# SCH_cube_2025-02-01.net
KiCad netlist of a schematic drawn in EasyEDA
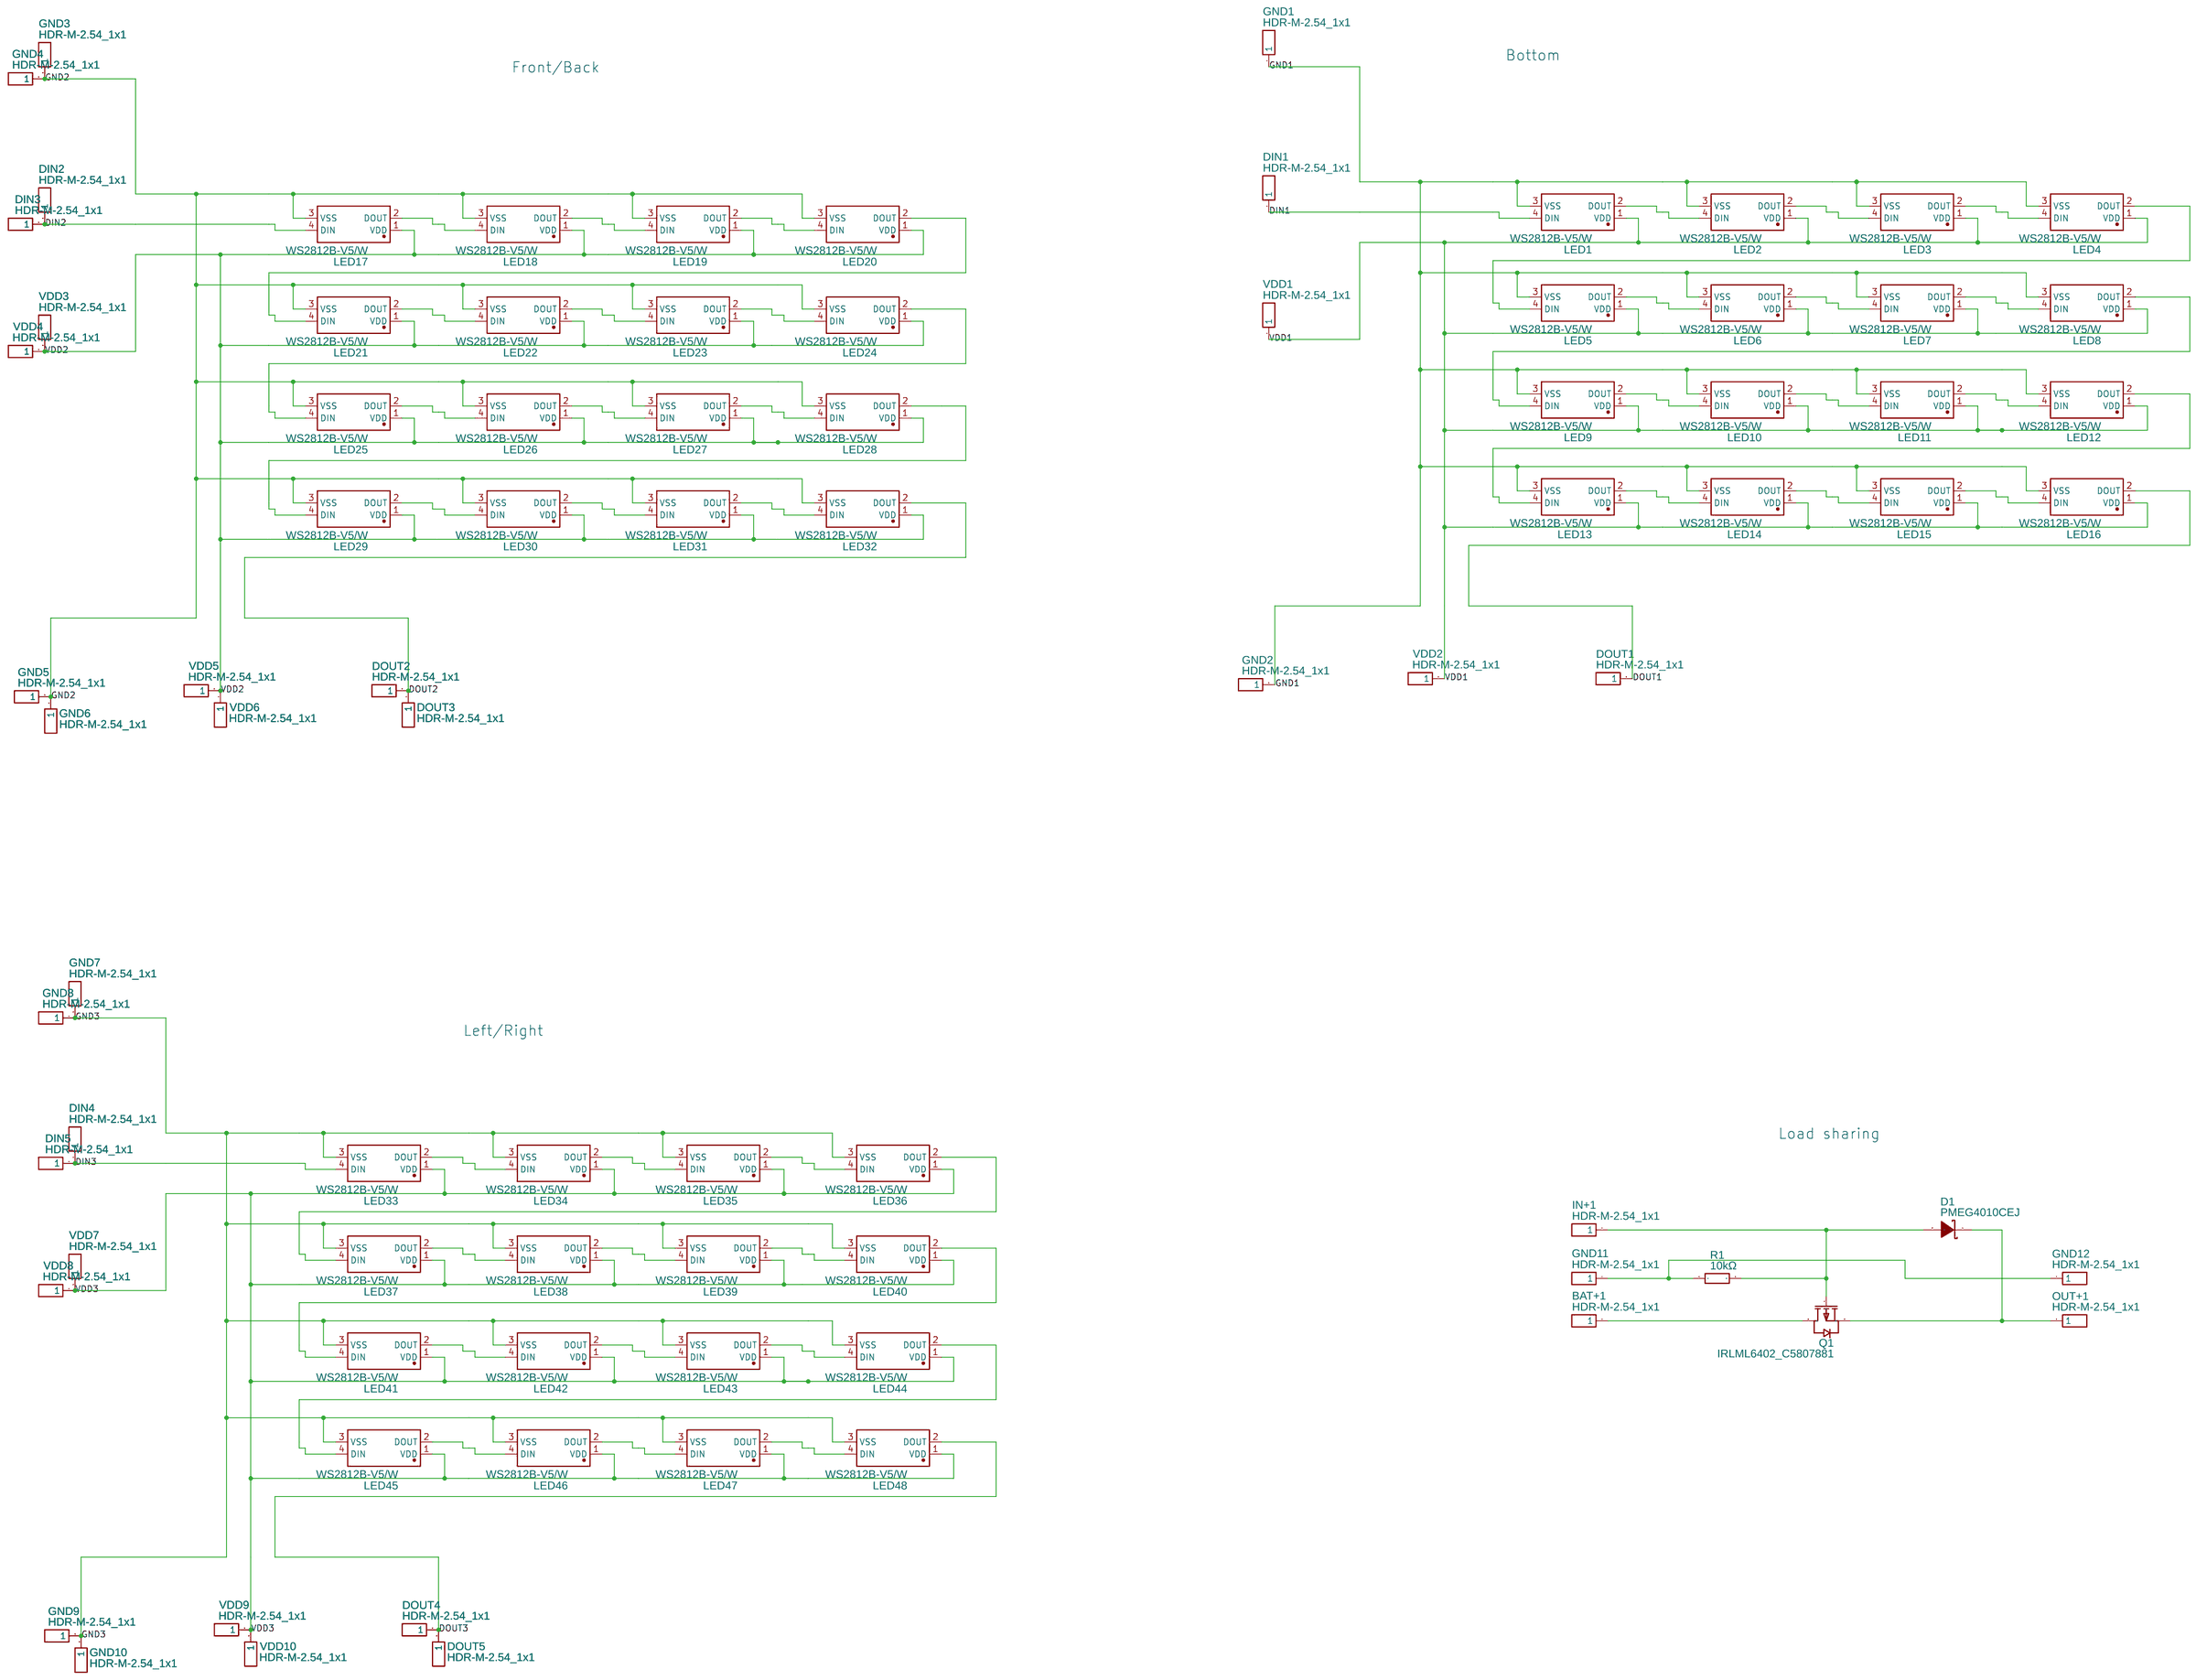
[diagram p0: schematic sheet]

(export (version "E")
  (design (tool "Eeschema 10.0.6"))
  (components
    (comp (ref "BAT+1") (value "HDR-M-2.54_1x1") (libsource (lib "") (part "HDR-M-2.54_1x1_12")))
    (comp (ref "D1")
      (value "PMEG4010CEJ")
      (fields
        (field (name "Manufacturer Part") "PMEG4010CEJ,115")
        (field (name "Manufacturer") "Nexperia(安世)")
      )
      (libsource (lib "") (part "PMEG4010CEJ"))
    )
    (comp (ref "DIN1") (value "HDR-M-2.54_1x1") (libsource (lib "") (part "HDR-M-2.54_1x1_4")))
    (comp (ref "DIN2") (value "HDR-M-2.54_1x1") (libsource (lib "") (part "HDR-M-2.54_1x1_4")))
    (comp (ref "DIN3") (value "HDR-M-2.54_1x1") (libsource (lib "") (part "HDR-M-2.54_1x1_3")))
    (comp (ref "DIN4") (value "HDR-M-2.54_1x1") (libsource (lib "") (part "HDR-M-2.54_1x1_4")))
    (comp (ref "DIN5") (value "HDR-M-2.54_1x1") (libsource (lib "") (part "HDR-M-2.54_1x1_3")))
    (comp (ref "DOUT1") (value "HDR-M-2.54_1x1") (libsource (lib "") (part "HDR-M-2.54_1x1_2")))
    (comp (ref "DOUT2") (value "HDR-M-2.54_1x1") (libsource (lib "") (part "HDR-M-2.54_1x1_2")))
    (comp (ref "DOUT3") (value "HDR-M-2.54_1x1") (libsource (lib "") (part "HDR-M-2.54_1x1_1")))
    (comp (ref "DOUT4") (value "HDR-M-2.54_1x1") (libsource (lib "") (part "HDR-M-2.54_1x1_2")))
    (comp (ref "DOUT5") (value "HDR-M-2.54_1x1") (libsource (lib "") (part "HDR-M-2.54_1x1_1")))
    (comp (ref "GND1") (value "HDR-M-2.54_1x1") (libsource (lib "") (part "HDR-M-2.54_1x1_6")))
    (comp (ref "GND2") (value "HDR-M-2.54_1x1") (libsource (lib "") (part "HDR-M-2.54_1x1_5")))
    (comp (ref "GND3") (value "HDR-M-2.54_1x1") (libsource (lib "") (part "HDR-M-2.54_1x1_6")))
    (comp (ref "GND4") (value "HDR-M-2.54_1x1") (libsource (lib "") (part "HDR-M-2.54_1x1_5")))
    (comp (ref "GND5") (value "HDR-M-2.54_1x1") (libsource (lib "") (part "HDR-M-2.54_1x1_5")))
    (comp (ref "GND6") (value "HDR-M-2.54_1x1") (libsource (lib "") (part "HDR-M-2.54_1x1_10")))
    (comp (ref "GND7") (value "HDR-M-2.54_1x1") (libsource (lib "") (part "HDR-M-2.54_1x1_6")))
    (comp (ref "GND8") (value "HDR-M-2.54_1x1") (libsource (lib "") (part "HDR-M-2.54_1x1_5")))
    (comp (ref "GND9") (value "HDR-M-2.54_1x1") (libsource (lib "") (part "HDR-M-2.54_1x1_5")))
    (comp (ref "GND10") (value "HDR-M-2.54_1x1") (libsource (lib "") (part "HDR-M-2.54_1x1_10")))
    (comp (ref "GND11") (value "HDR-M-2.54_1x1") (libsource (lib "") (part "HDR-M-2.54_1x1_5")))
    (comp (ref "GND12") (value "HDR-M-2.54_1x1") (libsource (lib "") (part "HDR-M-2.54_1x1_8")))
    (comp (ref "IN+1") (value "HDR-M-2.54_1x1") (libsource (lib "") (part "HDR-M-2.54_1x1_9")))
    (comp (ref "LED1")
      (value "WS2812B-V5/W")
      (fields (field (name "Manufacturer") "worldsemi"))
      (libsource (lib "") (part "WS2812B-V5/W"))
    )
    (comp (ref "LED2")
      (value "WS2812B-V5/W")
      (fields (field (name "Manufacturer") "worldsemi"))
      (libsource (lib "") (part "WS2812B-V5/W"))
    )
    (comp (ref "LED3")
      (value "WS2812B-V5/W")
      (fields (field (name "Manufacturer") "worldsemi"))
      (libsource (lib "") (part "WS2812B-V5/W"))
    )
    (comp (ref "LED4")
      (value "WS2812B-V5/W")
      (fields (field (name "Manufacturer") "worldsemi"))
      (libsource (lib "") (part "WS2812B-V5/W"))
    )
    (comp (ref "LED5")
      (value "WS2812B-V5/W")
      (fields (field (name "Manufacturer") "worldsemi"))
      (libsource (lib "") (part "WS2812B-V5/W"))
    )
    (comp (ref "LED6")
      (value "WS2812B-V5/W")
      (fields (field (name "Manufacturer") "worldsemi"))
      (libsource (lib "") (part "WS2812B-V5/W"))
    )
    (comp (ref "LED7")
      (value "WS2812B-V5/W")
      (fields (field (name "Manufacturer") "worldsemi"))
      (libsource (lib "") (part "WS2812B-V5/W"))
    )
    (comp (ref "LED8")
      (value "WS2812B-V5/W")
      (fields (field (name "Manufacturer") "worldsemi"))
      (libsource (lib "") (part "WS2812B-V5/W"))
    )
    (comp (ref "LED9")
      (value "WS2812B-V5/W")
      (fields (field (name "Manufacturer") "worldsemi"))
      (libsource (lib "") (part "WS2812B-V5/W"))
    )
    (comp (ref "LED10")
      (value "WS2812B-V5/W")
      (fields (field (name "Manufacturer") "worldsemi"))
      (libsource (lib "") (part "WS2812B-V5/W"))
    )
    (comp (ref "LED11")
      (value "WS2812B-V5/W")
      (fields (field (name "Manufacturer") "worldsemi"))
      (libsource (lib "") (part "WS2812B-V5/W"))
    )
    (comp (ref "LED12")
      (value "WS2812B-V5/W")
      (fields (field (name "Manufacturer") "worldsemi"))
      (libsource (lib "") (part "WS2812B-V5/W"))
    )
    (comp (ref "LED13")
      (value "WS2812B-V5/W")
      (fields (field (name "Manufacturer") "worldsemi"))
      (libsource (lib "") (part "WS2812B-V5/W"))
    )
    (comp (ref "LED14")
      (value "WS2812B-V5/W")
      (fields (field (name "Manufacturer") "worldsemi"))
      (libsource (lib "") (part "WS2812B-V5/W"))
    )
    (comp (ref "LED15")
      (value "WS2812B-V5/W")
      (fields (field (name "Manufacturer") "worldsemi"))
      (libsource (lib "") (part "WS2812B-V5/W"))
    )
    (comp (ref "LED16")
      (value "WS2812B-V5/W")
      (fields (field (name "Manufacturer") "worldsemi"))
      (libsource (lib "") (part "WS2812B-V5/W"))
    )
    (comp (ref "LED17")
      (value "WS2812B-V5/W")
      (fields (field (name "Manufacturer") "worldsemi"))
      (libsource (lib "") (part "WS2812B-V5/W"))
    )
    (comp (ref "LED18")
      (value "WS2812B-V5/W")
      (fields (field (name "Manufacturer") "worldsemi"))
      (libsource (lib "") (part "WS2812B-V5/W"))
    )
    (comp (ref "LED19")
      (value "WS2812B-V5/W")
      (fields (field (name "Manufacturer") "worldsemi"))
      (libsource (lib "") (part "WS2812B-V5/W"))
    )
    (comp (ref "LED20")
      (value "WS2812B-V5/W")
      (fields (field (name "Manufacturer") "worldsemi"))
      (libsource (lib "") (part "WS2812B-V5/W"))
    )
    (comp (ref "LED21")
      (value "WS2812B-V5/W")
      (fields (field (name "Manufacturer") "worldsemi"))
      (libsource (lib "") (part "WS2812B-V5/W"))
    )
    (comp (ref "LED22")
      (value "WS2812B-V5/W")
      (fields (field (name "Manufacturer") "worldsemi"))
      (libsource (lib "") (part "WS2812B-V5/W"))
    )
    (comp (ref "LED23")
      (value "WS2812B-V5/W")
      (fields (field (name "Manufacturer") "worldsemi"))
      (libsource (lib "") (part "WS2812B-V5/W"))
    )
    (comp (ref "LED24")
      (value "WS2812B-V5/W")
      (fields (field (name "Manufacturer") "worldsemi"))
      (libsource (lib "") (part "WS2812B-V5/W"))
    )
    (comp (ref "LED25")
      (value "WS2812B-V5/W")
      (fields (field (name "Manufacturer") "worldsemi"))
      (libsource (lib "") (part "WS2812B-V5/W"))
    )
    (comp (ref "LED26")
      (value "WS2812B-V5/W")
      (fields (field (name "Manufacturer") "worldsemi"))
      (libsource (lib "") (part "WS2812B-V5/W"))
    )
    (comp (ref "LED27")
      (value "WS2812B-V5/W")
      (fields (field (name "Manufacturer") "worldsemi"))
      (libsource (lib "") (part "WS2812B-V5/W"))
    )
    (comp (ref "LED28")
      (value "WS2812B-V5/W")
      (fields (field (name "Manufacturer") "worldsemi"))
      (libsource (lib "") (part "WS2812B-V5/W"))
    )
    (comp (ref "LED29")
      (value "WS2812B-V5/W")
      (fields (field (name "Manufacturer") "worldsemi"))
      (libsource (lib "") (part "WS2812B-V5/W"))
    )
    (comp (ref "LED30")
      (value "WS2812B-V5/W")
      (fields (field (name "Manufacturer") "worldsemi"))
      (libsource (lib "") (part "WS2812B-V5/W"))
    )
    (comp (ref "LED31")
      (value "WS2812B-V5/W")
      (fields (field (name "Manufacturer") "worldsemi"))
      (libsource (lib "") (part "WS2812B-V5/W"))
    )
    (comp (ref "LED32")
      (value "WS2812B-V5/W")
      (fields (field (name "Manufacturer") "worldsemi"))
      (libsource (lib "") (part "WS2812B-V5/W"))
    )
    (comp (ref "LED33")
      (value "WS2812B-V5/W")
      (fields (field (name "Manufacturer") "worldsemi"))
      (libsource (lib "") (part "WS2812B-V5/W"))
    )
    (comp (ref "LED34")
      (value "WS2812B-V5/W")
      (fields (field (name "Manufacturer") "worldsemi"))
      (libsource (lib "") (part "WS2812B-V5/W"))
    )
    (comp (ref "LED35")
      (value "WS2812B-V5/W")
      (fields (field (name "Manufacturer") "worldsemi"))
      (libsource (lib "") (part "WS2812B-V5/W"))
    )
    (comp (ref "LED36")
      (value "WS2812B-V5/W")
      (fields (field (name "Manufacturer") "worldsemi"))
      (libsource (lib "") (part "WS2812B-V5/W"))
    )
    (comp (ref "LED37")
      (value "WS2812B-V5/W")
      (fields (field (name "Manufacturer") "worldsemi"))
      (libsource (lib "") (part "WS2812B-V5/W"))
    )
    (comp (ref "LED38")
      (value "WS2812B-V5/W")
      (fields (field (name "Manufacturer") "worldsemi"))
      (libsource (lib "") (part "WS2812B-V5/W"))
    )
    (comp (ref "LED39")
      (value "WS2812B-V5/W")
      (fields (field (name "Manufacturer") "worldsemi"))
      (libsource (lib "") (part "WS2812B-V5/W"))
    )
    (comp (ref "LED40")
      (value "WS2812B-V5/W")
      (fields (field (name "Manufacturer") "worldsemi"))
      (libsource (lib "") (part "WS2812B-V5/W"))
    )
    (comp (ref "LED41")
      (value "WS2812B-V5/W")
      (fields (field (name "Manufacturer") "worldsemi"))
      (libsource (lib "") (part "WS2812B-V5/W"))
    )
    (comp (ref "LED42")
      (value "WS2812B-V5/W")
      (fields (field (name "Manufacturer") "worldsemi"))
      (libsource (lib "") (part "WS2812B-V5/W"))
    )
    (comp (ref "LED43")
      (value "WS2812B-V5/W")
      (fields (field (name "Manufacturer") "worldsemi"))
      (libsource (lib "") (part "WS2812B-V5/W"))
    )
    (comp (ref "LED44")
      (value "WS2812B-V5/W")
      (fields (field (name "Manufacturer") "worldsemi"))
      (libsource (lib "") (part "WS2812B-V5/W"))
    )
    (comp (ref "LED45")
      (value "WS2812B-V5/W")
      (fields (field (name "Manufacturer") "worldsemi"))
      (libsource (lib "") (part "WS2812B-V5/W"))
    )
    (comp (ref "LED46")
      (value "WS2812B-V5/W")
      (fields (field (name "Manufacturer") "worldsemi"))
      (libsource (lib "") (part "WS2812B-V5/W"))
    )
    (comp (ref "LED47")
      (value "WS2812B-V5/W")
      (fields (field (name "Manufacturer") "worldsemi"))
      (libsource (lib "") (part "WS2812B-V5/W"))
    )
    (comp (ref "LED48")
      (value "WS2812B-V5/W")
      (fields (field (name "Manufacturer") "worldsemi"))
      (libsource (lib "") (part "WS2812B-V5/W"))
    )
    (comp (ref "OUT+1") (value "HDR-M-2.54_1x1") (libsource (lib "") (part "HDR-M-2.54_1x1_13")))
    (comp (ref "Q1")
      (value "IRLML6402_C5807881")
      (fields (field (name "Manufacturer Part") "IRLML6402") (field (name "Manufacturer") "GOODWORK(固得沃克)"))
      (libsource (lib "") (part "IRLML6402_C5807881"))
    )
    (comp (ref "R1")
      (value "10kΩ")
      (fields
        (field (name "Manufacturer Part") "1206W4J0103T5E")
        (field (name "Manufacturer") "UNI-ROYAL(厚声)")
      )
      (libsource (lib "") (part "1206W4J0103T5E"))
    )
    (comp (ref "VDD1") (value "HDR-M-2.54_1x1") (libsource (lib "") (part "HDR-M-2.54_1x1_11")))
    (comp (ref "VDD2") (value "HDR-M-2.54_1x1") (libsource (lib "") (part "HDR-M-2.54_1x1_7")))
    (comp (ref "VDD3") (value "HDR-M-2.54_1x1") (libsource (lib "") (part "HDR-M-2.54_1x1_11")))
    (comp (ref "VDD4") (value "HDR-M-2.54_1x1") (libsource (lib "") (part "HDR-M-2.54_1x1_7")))
    (comp (ref "VDD5") (value "HDR-M-2.54_1x1") (libsource (lib "") (part "HDR-M-2.54_1x1_7")))
    (comp (ref "VDD6") (value "HDR-M-2.54_1x1") (libsource (lib "") (part "HDR-M-2.54_1x1")))
    (comp (ref "VDD7") (value "HDR-M-2.54_1x1") (libsource (lib "") (part "HDR-M-2.54_1x1_11")))
    (comp (ref "VDD8") (value "HDR-M-2.54_1x1") (libsource (lib "") (part "HDR-M-2.54_1x1_7")))
    (comp (ref "VDD9") (value "HDR-M-2.54_1x1") (libsource (lib "") (part "HDR-M-2.54_1x1_7")))
    (comp (ref "VDD10") (value "HDR-M-2.54_1x1") (libsource (lib "") (part "HDR-M-2.54_1x1")))
  )
  (nets
    (net (code "1") (name "/DIN1") (class "Default")
      (node (ref "DIN1") (pin "1") (pinfunction "1_1") (pintype "input"))
      (node (ref "LED1") (pin "4") (pinfunction "DIN_4") (pintype "unspecified"))
    )
    (net (code "2") (name "/DIN2") (class "Default")
      (node (ref "DIN2") (pin "1") (pinfunction "1_1") (pintype "input"))
      (node (ref "DIN3") (pin "1") (pinfunction "1_1") (pintype "input"))
      (node (ref "LED17") (pin "4") (pinfunction "DIN_4") (pintype "unspecified"))
    )
    (net (code "3") (name "/DIN3") (class "Default")
      (node (ref "DIN4") (pin "1") (pinfunction "1_1") (pintype "input"))
      (node (ref "DIN5") (pin "1") (pinfunction "1_1") (pintype "input"))
      (node (ref "LED33") (pin "4") (pinfunction "DIN_4") (pintype "unspecified"))
    )
    (net (code "4") (name "/DOUT1") (class "Default")
      (node (ref "DOUT1") (pin "1") (pinfunction "1_1") (pintype "input"))
      (node (ref "LED16") (pin "2") (pinfunction "DOUT_2") (pintype "unspecified"))
    )
    (net (code "5") (name "/DOUT2") (class "Default")
      (node (ref "DOUT2") (pin "1") (pinfunction "1_1") (pintype "input"))
      (node (ref "DOUT3") (pin "1") (pinfunction "1_1") (pintype "input"))
      (node (ref "LED32") (pin "2") (pinfunction "DOUT_2") (pintype "unspecified"))
    )
    (net (code "6") (name "/DOUT3") (class "Default")
      (node (ref "DOUT4") (pin "1") (pinfunction "1_1") (pintype "input"))
      (node (ref "DOUT5") (pin "1") (pinfunction "1_1") (pintype "input"))
      (node (ref "LED48") (pin "2") (pinfunction "DOUT_2") (pintype "unspecified"))
    )
    (net (code "7") (name "/GND1") (class "Default")
      (node (ref "GND1") (pin "1") (pinfunction "1_1") (pintype "input"))
      (node (ref "GND2") (pin "1") (pinfunction "1_1") (pintype "input"))
      (node (ref "LED1") (pin "3") (pinfunction "VSS_3") (pintype "unspecified"))
      (node (ref "LED10") (pin "3") (pinfunction "VSS_3") (pintype "unspecified"))
      (node (ref "LED11") (pin "3") (pinfunction "VSS_3") (pintype "unspecified"))
      (node (ref "LED12") (pin "3") (pinfunction "VSS_3") (pintype "unspecified"))
      (node (ref "LED13") (pin "3") (pinfunction "VSS_3") (pintype "unspecified"))
      (node (ref "LED14") (pin "3") (pinfunction "VSS_3") (pintype "unspecified"))
      (node (ref "LED15") (pin "3") (pinfunction "VSS_3") (pintype "unspecified"))
      (node (ref "LED16") (pin "3") (pinfunction "VSS_3") (pintype "unspecified"))
      (node (ref "LED2") (pin "3") (pinfunction "VSS_3") (pintype "unspecified"))
      (node (ref "LED3") (pin "3") (pinfunction "VSS_3") (pintype "unspecified"))
      (node (ref "LED4") (pin "3") (pinfunction "VSS_3") (pintype "unspecified"))
      (node (ref "LED5") (pin "3") (pinfunction "VSS_3") (pintype "unspecified"))
      (node (ref "LED6") (pin "3") (pinfunction "VSS_3") (pintype "unspecified"))
      (node (ref "LED7") (pin "3") (pinfunction "VSS_3") (pintype "unspecified"))
      (node (ref "LED8") (pin "3") (pinfunction "VSS_3") (pintype "unspecified"))
      (node (ref "LED9") (pin "3") (pinfunction "VSS_3") (pintype "unspecified"))
    )
    (net (code "8") (name "/GND2") (class "Default")
      (node (ref "GND3") (pin "1") (pinfunction "1_1") (pintype "input"))
      (node (ref "GND4") (pin "1") (pinfunction "1_1") (pintype "input"))
      (node (ref "GND5") (pin "1") (pinfunction "1_1") (pintype "input"))
      (node (ref "GND6") (pin "1") (pinfunction "1_1") (pintype "input"))
      (node (ref "LED17") (pin "3") (pinfunction "VSS_3") (pintype "unspecified"))
      (node (ref "LED18") (pin "3") (pinfunction "VSS_3") (pintype "unspecified"))
      (node (ref "LED19") (pin "3") (pinfunction "VSS_3") (pintype "unspecified"))
      (node (ref "LED20") (pin "3") (pinfunction "VSS_3") (pintype "unspecified"))
      (node (ref "LED21") (pin "3") (pinfunction "VSS_3") (pintype "unspecified"))
      (node (ref "LED22") (pin "3") (pinfunction "VSS_3") (pintype "unspecified"))
      (node (ref "LED23") (pin "3") (pinfunction "VSS_3") (pintype "unspecified"))
      (node (ref "LED24") (pin "3") (pinfunction "VSS_3") (pintype "unspecified"))
      (node (ref "LED25") (pin "3") (pinfunction "VSS_3") (pintype "unspecified"))
      (node (ref "LED26") (pin "3") (pinfunction "VSS_3") (pintype "unspecified"))
      (node (ref "LED27") (pin "3") (pinfunction "VSS_3") (pintype "unspecified"))
      (node (ref "LED28") (pin "3") (pinfunction "VSS_3") (pintype "unspecified"))
      (node (ref "LED29") (pin "3") (pinfunction "VSS_3") (pintype "unspecified"))
      (node (ref "LED30") (pin "3") (pinfunction "VSS_3") (pintype "unspecified"))
      (node (ref "LED31") (pin "3") (pinfunction "VSS_3") (pintype "unspecified"))
      (node (ref "LED32") (pin "3") (pinfunction "VSS_3") (pintype "unspecified"))
    )
    (net (code "9") (name "/GND3") (class "Default")
      (node (ref "GND10") (pin "1") (pinfunction "1_1") (pintype "input"))
      (node (ref "GND7") (pin "1") (pinfunction "1_1") (pintype "input"))
      (node (ref "GND8") (pin "1") (pinfunction "1_1") (pintype "input"))
      (node (ref "GND9") (pin "1") (pinfunction "1_1") (pintype "input"))
      (node (ref "LED33") (pin "3") (pinfunction "VSS_3") (pintype "unspecified"))
      (node (ref "LED34") (pin "3") (pinfunction "VSS_3") (pintype "unspecified"))
      (node (ref "LED35") (pin "3") (pinfunction "VSS_3") (pintype "unspecified"))
      (node (ref "LED36") (pin "3") (pinfunction "VSS_3") (pintype "unspecified"))
      (node (ref "LED37") (pin "3") (pinfunction "VSS_3") (pintype "unspecified"))
      (node (ref "LED38") (pin "3") (pinfunction "VSS_3") (pintype "unspecified"))
      (node (ref "LED39") (pin "3") (pinfunction "VSS_3") (pintype "unspecified"))
      (node (ref "LED40") (pin "3") (pinfunction "VSS_3") (pintype "unspecified"))
      (node (ref "LED41") (pin "3") (pinfunction "VSS_3") (pintype "unspecified"))
      (node (ref "LED42") (pin "3") (pinfunction "VSS_3") (pintype "unspecified"))
      (node (ref "LED43") (pin "3") (pinfunction "VSS_3") (pintype "unspecified"))
      (node (ref "LED44") (pin "3") (pinfunction "VSS_3") (pintype "unspecified"))
      (node (ref "LED45") (pin "3") (pinfunction "VSS_3") (pintype "unspecified"))
      (node (ref "LED46") (pin "3") (pinfunction "VSS_3") (pintype "unspecified"))
      (node (ref "LED47") (pin "3") (pinfunction "VSS_3") (pintype "unspecified"))
      (node (ref "LED48") (pin "3") (pinfunction "VSS_3") (pintype "unspecified"))
    )
    (net (code "10") (name "/VDD1") (class "Default")
      (node (ref "LED1") (pin "1") (pinfunction "VDD_1") (pintype "unspecified"))
      (node (ref "LED10") (pin "1") (pinfunction "VDD_1") (pintype "unspecified"))
      (node (ref "LED11") (pin "1") (pinfunction "VDD_1") (pintype "unspecified"))
      (node (ref "LED12") (pin "1") (pinfunction "VDD_1") (pintype "unspecified"))
      (node (ref "LED13") (pin "1") (pinfunction "VDD_1") (pintype "unspecified"))
      (node (ref "LED14") (pin "1") (pinfunction "VDD_1") (pintype "unspecified"))
      (node (ref "LED15") (pin "1") (pinfunction "VDD_1") (pintype "unspecified"))
      (node (ref "LED16") (pin "1") (pinfunction "VDD_1") (pintype "unspecified"))
      (node (ref "LED2") (pin "1") (pinfunction "VDD_1") (pintype "unspecified"))
      (node (ref "LED3") (pin "1") (pinfunction "VDD_1") (pintype "unspecified"))
      (node (ref "LED4") (pin "1") (pinfunction "VDD_1") (pintype "unspecified"))
      (node (ref "LED5") (pin "1") (pinfunction "VDD_1") (pintype "unspecified"))
      (node (ref "LED6") (pin "1") (pinfunction "VDD_1") (pintype "unspecified"))
      (node (ref "LED7") (pin "1") (pinfunction "VDD_1") (pintype "unspecified"))
      (node (ref "LED8") (pin "1") (pinfunction "VDD_1") (pintype "unspecified"))
      (node (ref "LED9") (pin "1") (pinfunction "VDD_1") (pintype "unspecified"))
      (node (ref "VDD1") (pin "1") (pinfunction "1_1") (pintype "input"))
      (node (ref "VDD2") (pin "1") (pinfunction "1_1") (pintype "input"))
    )
    (net (code "11") (name "/VDD2") (class "Default")
      (node (ref "LED17") (pin "1") (pinfunction "VDD_1") (pintype "unspecified"))
      (node (ref "LED18") (pin "1") (pinfunction "VDD_1") (pintype "unspecified"))
      (node (ref "LED19") (pin "1") (pinfunction "VDD_1") (pintype "unspecified"))
      (node (ref "LED20") (pin "1") (pinfunction "VDD_1") (pintype "unspecified"))
      (node (ref "LED21") (pin "1") (pinfunction "VDD_1") (pintype "unspecified"))
      (node (ref "LED22") (pin "1") (pinfunction "VDD_1") (pintype "unspecified"))
      (node (ref "LED23") (pin "1") (pinfunction "VDD_1") (pintype "unspecified"))
      (node (ref "LED24") (pin "1") (pinfunction "VDD_1") (pintype "unspecified"))
      (node (ref "LED25") (pin "1") (pinfunction "VDD_1") (pintype "unspecified"))
      (node (ref "LED26") (pin "1") (pinfunction "VDD_1") (pintype "unspecified"))
      (node (ref "LED27") (pin "1") (pinfunction "VDD_1") (pintype "unspecified"))
      (node (ref "LED28") (pin "1") (pinfunction "VDD_1") (pintype "unspecified"))
      (node (ref "LED29") (pin "1") (pinfunction "VDD_1") (pintype "unspecified"))
      (node (ref "LED30") (pin "1") (pinfunction "VDD_1") (pintype "unspecified"))
      (node (ref "LED31") (pin "1") (pinfunction "VDD_1") (pintype "unspecified"))
      (node (ref "LED32") (pin "1") (pinfunction "VDD_1") (pintype "unspecified"))
      (node (ref "VDD3") (pin "1") (pinfunction "1_1") (pintype "input"))
      (node (ref "VDD4") (pin "1") (pinfunction "1_1") (pintype "input"))
      (node (ref "VDD5") (pin "1") (pinfunction "1_1") (pintype "input"))
      (node (ref "VDD6") (pin "1") (pinfunction "1_1") (pintype "input"))
    )
    (net (code "12") (name "/VDD3") (class "Default")
      (node (ref "LED33") (pin "1") (pinfunction "VDD_1") (pintype "unspecified"))
      (node (ref "LED34") (pin "1") (pinfunction "VDD_1") (pintype "unspecified"))
      (node (ref "LED35") (pin "1") (pinfunction "VDD_1") (pintype "unspecified"))
      (node (ref "LED36") (pin "1") (pinfunction "VDD_1") (pintype "unspecified"))
      (node (ref "LED37") (pin "1") (pinfunction "VDD_1") (pintype "unspecified"))
      (node (ref "LED38") (pin "1") (pinfunction "VDD_1") (pintype "unspecified"))
      (node (ref "LED39") (pin "1") (pinfunction "VDD_1") (pintype "unspecified"))
      (node (ref "LED40") (pin "1") (pinfunction "VDD_1") (pintype "unspecified"))
      (node (ref "LED41") (pin "1") (pinfunction "VDD_1") (pintype "unspecified"))
      (node (ref "LED42") (pin "1") (pinfunction "VDD_1") (pintype "unspecified"))
      (node (ref "LED43") (pin "1") (pinfunction "VDD_1") (pintype "unspecified"))
      (node (ref "LED44") (pin "1") (pinfunction "VDD_1") (pintype "unspecified"))
      (node (ref "LED45") (pin "1") (pinfunction "VDD_1") (pintype "unspecified"))
      (node (ref "LED46") (pin "1") (pinfunction "VDD_1") (pintype "unspecified"))
      (node (ref "LED47") (pin "1") (pinfunction "VDD_1") (pintype "unspecified"))
      (node (ref "LED48") (pin "1") (pinfunction "VDD_1") (pintype "unspecified"))
      (node (ref "VDD10") (pin "1") (pinfunction "1_1") (pintype "input"))
      (node (ref "VDD7") (pin "1") (pinfunction "1_1") (pintype "input"))
      (node (ref "VDD8") (pin "1") (pinfunction "1_1") (pintype "input"))
      (node (ref "VDD9") (pin "1") (pinfunction "1_1") (pintype "input"))
    )
    (net (code "13") (name "Net-(D1-A)") (class "Default")
      (node (ref "D1") (pin "2") (pinfunction "A_2") (pintype "unspecified"))
      (node (ref "IN+1") (pin "1") (pinfunction "1_1") (pintype "input"))
      (node (ref "Q1") (pin "1") (pinfunction "G_1") (pintype "unspecified"))
      (node (ref "R1") (pin "2") (pinfunction "2_2") (pintype "input"))
    )
    (net (code "14") (name "Net-(D1-C)") (class "Default")
      (node (ref "D1") (pin "1") (pinfunction "C_1") (pintype "unspecified"))
      (node (ref "OUT+1") (pin "1") (pinfunction "1_1") (pintype "input"))
      (node (ref "Q1") (pin "2") (pinfunction "S_2") (pintype "unspecified"))
    )
    (net (code "15") (name "Net-(GND11-Pad1)") (class "Default")
      (node (ref "GND11") (pin "1") (pinfunction "1_1") (pintype "input"))
      (node (ref "GND12") (pin "1") (pinfunction "1_1") (pintype "input"))
      (node (ref "R1") (pin "1") (pinfunction "1_1") (pintype "input"))
    )
    (net (code "16") (name "Net-(LED1-DOUT)") (class "Default")
      (node (ref "LED1") (pin "2") (pinfunction "DOUT_2") (pintype "unspecified"))
      (node (ref "LED2") (pin "4") (pinfunction "DIN_4") (pintype "unspecified"))
    )
    (net (code "17") (name "Net-(LED2-DOUT)") (class "Default")
      (node (ref "LED2") (pin "2") (pinfunction "DOUT_2") (pintype "unspecified"))
      (node (ref "LED3") (pin "4") (pinfunction "DIN_4") (pintype "unspecified"))
    )
    (net (code "18") (name "Net-(LED3-DOUT)") (class "Default")
      (node (ref "LED3") (pin "2") (pinfunction "DOUT_2") (pintype "unspecified"))
      (node (ref "LED4") (pin "4") (pinfunction "DIN_4") (pintype "unspecified"))
    )
    (net (code "19") (name "Net-(LED4-DOUT)") (class "Default")
      (node (ref "LED4") (pin "2") (pinfunction "DOUT_2") (pintype "unspecified"))
      (node (ref "LED5") (pin "4") (pinfunction "DIN_4") (pintype "unspecified"))
    )
    (net (code "20") (name "Net-(LED5-DOUT)") (class "Default")
      (node (ref "LED5") (pin "2") (pinfunction "DOUT_2") (pintype "unspecified"))
      (node (ref "LED6") (pin "4") (pinfunction "DIN_4") (pintype "unspecified"))
    )
    (net (code "21") (name "Net-(LED6-DOUT)") (class "Default")
      (node (ref "LED6") (pin "2") (pinfunction "DOUT_2") (pintype "unspecified"))
      (node (ref "LED7") (pin "4") (pinfunction "DIN_4") (pintype "unspecified"))
    )
    (net (code "22") (name "Net-(LED7-DOUT)") (class "Default")
      (node (ref "LED7") (pin "2") (pinfunction "DOUT_2") (pintype "unspecified"))
      (node (ref "LED8") (pin "4") (pinfunction "DIN_4") (pintype "unspecified"))
    )
    (net (code "23") (name "Net-(LED8-DOUT)") (class "Default")
      (node (ref "LED8") (pin "2") (pinfunction "DOUT_2") (pintype "unspecified"))
      (node (ref "LED9") (pin "4") (pinfunction "DIN_4") (pintype "unspecified"))
    )
    (net (code "24") (name "Net-(LED10-DIN)") (class "Default")
      (node (ref "LED10") (pin "4") (pinfunction "DIN_4") (pintype "unspecified"))
      (node (ref "LED9") (pin "2") (pinfunction "DOUT_2") (pintype "unspecified"))
    )
    (net (code "25") (name "Net-(LED10-DOUT)") (class "Default")
      (node (ref "LED10") (pin "2") (pinfunction "DOUT_2") (pintype "unspecified"))
      (node (ref "LED11") (pin "4") (pinfunction "DIN_4") (pintype "unspecified"))
    )
    (net (code "26") (name "Net-(LED11-DOUT)") (class "Default")
      (node (ref "LED11") (pin "2") (pinfunction "DOUT_2") (pintype "unspecified"))
      (node (ref "LED12") (pin "4") (pinfunction "DIN_4") (pintype "unspecified"))
    )
    (net (code "27") (name "Net-(LED12-DOUT)") (class "Default")
      (node (ref "LED12") (pin "2") (pinfunction "DOUT_2") (pintype "unspecified"))
      (node (ref "LED13") (pin "4") (pinfunction "DIN_4") (pintype "unspecified"))
    )
    (net (code "28") (name "Net-(LED13-DOUT)") (class "Default")
      (node (ref "LED13") (pin "2") (pinfunction "DOUT_2") (pintype "unspecified"))
      (node (ref "LED14") (pin "4") (pinfunction "DIN_4") (pintype "unspecified"))
    )
    (net (code "29") (name "Net-(LED14-DOUT)") (class "Default")
      (node (ref "LED14") (pin "2") (pinfunction "DOUT_2") (pintype "unspecified"))
      (node (ref "LED15") (pin "4") (pinfunction "DIN_4") (pintype "unspecified"))
    )
    (net (code "30") (name "Net-(LED15-DOUT)") (class "Default")
      (node (ref "LED15") (pin "2") (pinfunction "DOUT_2") (pintype "unspecified"))
      (node (ref "LED16") (pin "4") (pinfunction "DIN_4") (pintype "unspecified"))
    )
    (net (code "31") (name "Net-(LED17-DOUT)") (class "Default")
      (node (ref "LED17") (pin "2") (pinfunction "DOUT_2") (pintype "unspecified"))
      (node (ref "LED18") (pin "4") (pinfunction "DIN_4") (pintype "unspecified"))
    )
    (net (code "32") (name "Net-(LED18-DOUT)") (class "Default")
      (node (ref "LED18") (pin "2") (pinfunction "DOUT_2") (pintype "unspecified"))
      (node (ref "LED19") (pin "4") (pinfunction "DIN_4") (pintype "unspecified"))
    )
    (net (code "33") (name "Net-(LED19-DOUT)") (class "Default")
      (node (ref "LED19") (pin "2") (pinfunction "DOUT_2") (pintype "unspecified"))
      (node (ref "LED20") (pin "4") (pinfunction "DIN_4") (pintype "unspecified"))
    )
    (net (code "34") (name "Net-(LED20-DOUT)") (class "Default")
      (node (ref "LED20") (pin "2") (pinfunction "DOUT_2") (pintype "unspecified"))
      (node (ref "LED21") (pin "4") (pinfunction "DIN_4") (pintype "unspecified"))
    )
    (net (code "35") (name "Net-(LED21-DOUT)") (class "Default")
      (node (ref "LED21") (pin "2") (pinfunction "DOUT_2") (pintype "unspecified"))
      (node (ref "LED22") (pin "4") (pinfunction "DIN_4") (pintype "unspecified"))
    )
    (net (code "36") (name "Net-(LED22-DOUT)") (class "Default")
      (node (ref "LED22") (pin "2") (pinfunction "DOUT_2") (pintype "unspecified"))
      (node (ref "LED23") (pin "4") (pinfunction "DIN_4") (pintype "unspecified"))
    )
    (net (code "37") (name "Net-(LED23-DOUT)") (class "Default")
      (node (ref "LED23") (pin "2") (pinfunction "DOUT_2") (pintype "unspecified"))
      (node (ref "LED24") (pin "4") (pinfunction "DIN_4") (pintype "unspecified"))
    )
    (net (code "38") (name "Net-(LED24-DOUT)") (class "Default")
      (node (ref "LED24") (pin "2") (pinfunction "DOUT_2") (pintype "unspecified"))
      (node (ref "LED25") (pin "4") (pinfunction "DIN_4") (pintype "unspecified"))
    )
    (net (code "39") (name "Net-(LED25-DOUT)") (class "Default")
      (node (ref "LED25") (pin "2") (pinfunction "DOUT_2") (pintype "unspecified"))
      (node (ref "LED26") (pin "4") (pinfunction "DIN_4") (pintype "unspecified"))
    )
    (net (code "40") (name "Net-(LED26-DOUT)") (class "Default")
      (node (ref "LED26") (pin "2") (pinfunction "DOUT_2") (pintype "unspecified"))
      (node (ref "LED27") (pin "4") (pinfunction "DIN_4") (pintype "unspecified"))
    )
    (net (code "41") (name "Net-(LED27-DOUT)") (class "Default")
      (node (ref "LED27") (pin "2") (pinfunction "DOUT_2") (pintype "unspecified"))
      (node (ref "LED28") (pin "4") (pinfunction "DIN_4") (pintype "unspecified"))
    )
    (net (code "42") (name "Net-(LED28-DOUT)") (class "Default")
      (node (ref "LED28") (pin "2") (pinfunction "DOUT_2") (pintype "unspecified"))
      (node (ref "LED29") (pin "4") (pinfunction "DIN_4") (pintype "unspecified"))
    )
    (net (code "43") (name "Net-(LED29-DOUT)") (class "Default")
      (node (ref "LED29") (pin "2") (pinfunction "DOUT_2") (pintype "unspecified"))
      (node (ref "LED30") (pin "4") (pinfunction "DIN_4") (pintype "unspecified"))
    )
    (net (code "44") (name "Net-(LED30-DOUT)") (class "Default")
      (node (ref "LED30") (pin "2") (pinfunction "DOUT_2") (pintype "unspecified"))
      (node (ref "LED31") (pin "4") (pinfunction "DIN_4") (pintype "unspecified"))
    )
    (net (code "45") (name "Net-(LED31-DOUT)") (class "Default")
      (node (ref "LED31") (pin "2") (pinfunction "DOUT_2") (pintype "unspecified"))
      (node (ref "LED32") (pin "4") (pinfunction "DIN_4") (pintype "unspecified"))
    )
    (net (code "46") (name "Net-(LED33-DOUT)") (class "Default")
      (node (ref "LED33") (pin "2") (pinfunction "DOUT_2") (pintype "unspecified"))
      (node (ref "LED34") (pin "4") (pinfunction "DIN_4") (pintype "unspecified"))
    )
    (net (code "47") (name "Net-(LED34-DOUT)") (class "Default")
      (node (ref "LED34") (pin "2") (pinfunction "DOUT_2") (pintype "unspecified"))
      (node (ref "LED35") (pin "4") (pinfunction "DIN_4") (pintype "unspecified"))
    )
    (net (code "48") (name "Net-(LED35-DOUT)") (class "Default")
      (node (ref "LED35") (pin "2") (pinfunction "DOUT_2") (pintype "unspecified"))
      (node (ref "LED36") (pin "4") (pinfunction "DIN_4") (pintype "unspecified"))
    )
    (net (code "49") (name "Net-(LED36-DOUT)") (class "Default")
      (node (ref "LED36") (pin "2") (pinfunction "DOUT_2") (pintype "unspecified"))
      (node (ref "LED37") (pin "4") (pinfunction "DIN_4") (pintype "unspecified"))
    )
    (net (code "50") (name "Net-(LED37-DOUT)") (class "Default")
      (node (ref "LED37") (pin "2") (pinfunction "DOUT_2") (pintype "unspecified"))
      (node (ref "LED38") (pin "4") (pinfunction "DIN_4") (pintype "unspecified"))
    )
    (net (code "51") (name "Net-(LED38-DOUT)") (class "Default")
      (node (ref "LED38") (pin "2") (pinfunction "DOUT_2") (pintype "unspecified"))
      (node (ref "LED39") (pin "4") (pinfunction "DIN_4") (pintype "unspecified"))
    )
    (net (code "52") (name "Net-(LED39-DOUT)") (class "Default")
      (node (ref "LED39") (pin "2") (pinfunction "DOUT_2") (pintype "unspecified"))
      (node (ref "LED40") (pin "4") (pinfunction "DIN_4") (pintype "unspecified"))
    )
    (net (code "53") (name "Net-(LED40-DOUT)") (class "Default")
      (node (ref "LED40") (pin "2") (pinfunction "DOUT_2") (pintype "unspecified"))
      (node (ref "LED41") (pin "4") (pinfunction "DIN_4") (pintype "unspecified"))
    )
    (net (code "54") (name "Net-(LED41-DOUT)") (class "Default")
      (node (ref "LED41") (pin "2") (pinfunction "DOUT_2") (pintype "unspecified"))
      (node (ref "LED42") (pin "4") (pinfunction "DIN_4") (pintype "unspecified"))
    )
    (net (code "55") (name "Net-(LED42-DOUT)") (class "Default")
      (node (ref "LED42") (pin "2") (pinfunction "DOUT_2") (pintype "unspecified"))
      (node (ref "LED43") (pin "4") (pinfunction "DIN_4") (pintype "unspecified"))
    )
    (net (code "56") (name "Net-(LED43-DOUT)") (class "Default")
      (node (ref "LED43") (pin "2") (pinfunction "DOUT_2") (pintype "unspecified"))
      (node (ref "LED44") (pin "4") (pinfunction "DIN_4") (pintype "unspecified"))
    )
    (net (code "57") (name "Net-(LED44-DOUT)") (class "Default")
      (node (ref "LED44") (pin "2") (pinfunction "DOUT_2") (pintype "unspecified"))
      (node (ref "LED45") (pin "4") (pinfunction "DIN_4") (pintype "unspecified"))
    )
    (net (code "58") (name "Net-(LED45-DOUT)") (class "Default")
      (node (ref "LED45") (pin "2") (pinfunction "DOUT_2") (pintype "unspecified"))
      (node (ref "LED46") (pin "4") (pinfunction "DIN_4") (pintype "unspecified"))
    )
    (net (code "59") (name "Net-(LED46-DOUT)") (class "Default")
      (node (ref "LED46") (pin "2") (pinfunction "DOUT_2") (pintype "unspecified"))
      (node (ref "LED47") (pin "4") (pinfunction "DIN_4") (pintype "unspecified"))
    )
    (net (code "60") (name "Net-(LED47-DOUT)") (class "Default")
      (node (ref "LED47") (pin "2") (pinfunction "DOUT_2") (pintype "unspecified"))
      (node (ref "LED48") (pin "4") (pinfunction "DIN_4") (pintype "unspecified"))
    )
    (net (code "61") (name "Net-(Q1-D)") (class "Default")
      (node (ref "BAT+1") (pin "1") (pinfunction "1_1") (pintype "input"))
      (node (ref "Q1") (pin "3") (pinfunction "D_3") (pintype "unspecified"))
    )
  )
)
